# MOSFET_Driver_Sheet1.net
KiCad netlist of a schematic drawn in Altium Designer
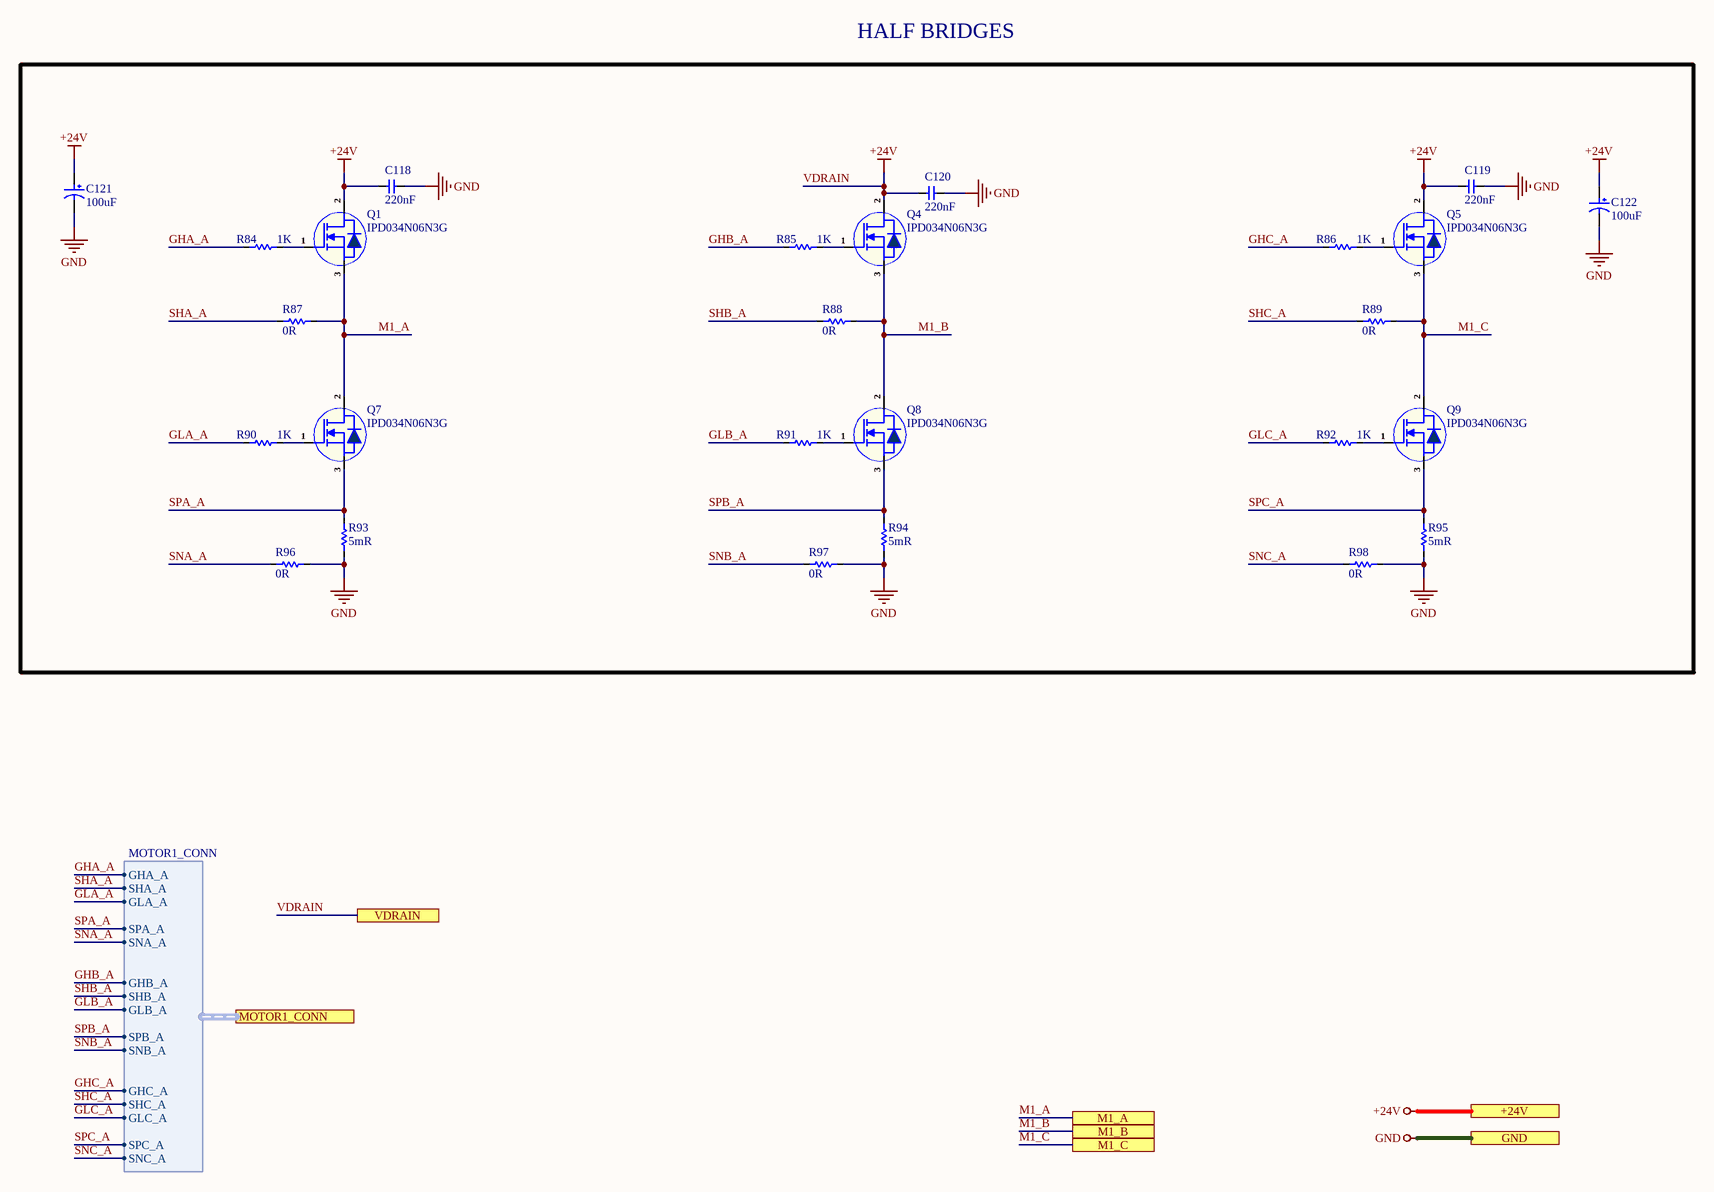
[diagram p0: MOSFET_Driver_Sheet1.SchDoc]

(export (version "E")
  (design (tool "Eeschema 10.0.6"))
  (components
    (comp (ref "C118")
      (value "220nF")
      (footprint "Cap-0805")
      (description "CAP CER 0.22UF 100V X7R 0805")
      (fields
        (field (name "MANUFACTURER") "Kyocera AVX")
        (field (name "MANUFACTURER PART NUMBER") "08051C224K4T2A")
      )
      (libsource (lib "eSpark Libraries") (part "08051C224K4T2A"))
    )
    (comp (ref "C119")
      (value "220nF")
      (footprint "Cap-0805")
      (description "CAP CER 0.22UF 100V X7R 0805")
      (fields
        (field (name "MANUFACTURER") "Kyocera AVX")
        (field (name "MANUFACTURER PART NUMBER") "08051C224K4T2A")
      )
      (libsource (lib "eSpark Libraries") (part "08051C224K4T2A"))
    )
    (comp (ref "C120")
      (value "220nF")
      (footprint "Cap-0805")
      (description "CAP CER 0.22UF 100V X7R 0805")
      (fields
        (field (name "MANUFACTURER") "Kyocera AVX")
        (field (name "MANUFACTURER PART NUMBER") "08051C224K4T2A")
      )
      (libsource (lib "eSpark Libraries") (part "08051C224K4T2A"))
    )
    (comp (ref "C121")
      (value "100uF")
      (footprint "RVT1A101M0605")
      (description "100uF 10V 55mA@120Hz ±20% SMD,D6.3xL5.4mm Aluminum Electrolytic Capacitors - SMD ROHS")
      (fields
        (field (name "MANUFACTURER") "ROQANG")
        (field (name "MANUFACTURER PART NUMBER") "RVT1A101M0605")
      )
      (libsource (lib "eSpark Libraries") (part "RVT1A101M0605"))
    )
    (comp (ref "C122")
      (value "100uF")
      (footprint "RVT1A101M0605")
      (description "100uF 10V 55mA@120Hz ±20% SMD,D6.3xL5.4mm Aluminum Electrolytic Capacitors - SMD ROHS")
      (fields
        (field (name "MANUFACTURER") "ROQANG")
        (field (name "MANUFACTURER PART NUMBER") "RVT1A101M0605")
      )
      (libsource (lib "eSpark Libraries") (part "RVT1A101M0605"))
    )
    (comp (ref "Q1")
      (value "IPD034N06N3G")
      (footprint "TO-252-2L")
      (description "MOSFET N-CH 60V 100A TO252-3")
      (fields (field (name "MANUFACTURER") "Infineon") (field (name "LCSC PART NUMBER") "C94897"))
      (libsource (lib "eSpark Libraries") (part "IPD034N06N3G"))
    )
    (comp (ref "Q4")
      (value "IPD034N06N3G")
      (footprint "TO-252-2L")
      (description "MOSFET N-CH 60V 100A TO252-3")
      (fields (field (name "MANUFACTURER") "Infineon") (field (name "LCSC PART NUMBER") "C94897"))
      (libsource (lib "eSpark Libraries") (part "IPD034N06N3G"))
    )
    (comp (ref "Q5")
      (value "IPD034N06N3G")
      (footprint "TO-252-2L")
      (description "MOSFET N-CH 60V 100A TO252-3")
      (fields (field (name "MANUFACTURER") "Infineon") (field (name "LCSC PART NUMBER") "C94897"))
      (libsource (lib "eSpark Libraries") (part "IPD034N06N3G"))
    )
    (comp (ref "Q7")
      (value "IPD034N06N3G")
      (footprint "TO-252-2L")
      (description "MOSFET N-CH 60V 100A TO252-3")
      (fields (field (name "MANUFACTURER") "Infineon") (field (name "LCSC PART NUMBER") "C94897"))
      (libsource (lib "eSpark Libraries") (part "IPD034N06N3G"))
    )
    (comp (ref "Q8")
      (value "IPD034N06N3G")
      (footprint "TO-252-2L")
      (description "MOSFET N-CH 60V 100A TO252-3")
      (fields (field (name "MANUFACTURER") "Infineon") (field (name "LCSC PART NUMBER") "C94897"))
      (libsource (lib "eSpark Libraries") (part "IPD034N06N3G"))
    )
    (comp (ref "Q9")
      (value "IPD034N06N3G")
      (footprint "TO-252-2L")
      (description "MOSFET N-CH 60V 100A TO252-3")
      (fields (field (name "MANUFACTURER") "Infineon") (field (name "LCSC PART NUMBER") "C94897"))
      (libsource (lib "eSpark Libraries") (part "IPD034N06N3G"))
    )
    (comp (ref "R84")
      (value "1K")
      (footprint "Res-0402")
      (description "RES 1K OHM 1% 1/16W 0402")
      (fields
        (field (name "MANUFACTURER") "Yageo")
        (field (name "MANUFACTURER PART NUMBER") "RC0402FR-071KL")
      )
      (libsource (lib "eSpark Libraries") (part "RC0402FR-071KL"))
    )
    (comp (ref "R85")
      (value "1K")
      (footprint "Res-0402")
      (description "RES 1K OHM 1% 1/16W 0402")
      (fields
        (field (name "MANUFACTURER") "Yageo")
        (field (name "MANUFACTURER PART NUMBER") "RC0402FR-071KL")
      )
      (libsource (lib "eSpark Libraries") (part "RC0402FR-071KL"))
    )
    (comp (ref "R86")
      (value "1K")
      (footprint "Res-0402")
      (description "RES 1K OHM 1% 1/16W 0402")
      (fields
        (field (name "MANUFACTURER") "Yageo")
        (field (name "MANUFACTURER PART NUMBER") "RC0402FR-071KL")
      )
      (libsource (lib "eSpark Libraries") (part "RC0402FR-071KL"))
    )
    (comp (ref "R87")
      (value "0R")
      (footprint "Res-0603")
      (description "RES 0 OHM JUMPER 1/10W 0603")
      (fields
        (field (name "MANUFACTURER") "Yageo")
        (field (name "MANUFACTURER PART NUMBER") "RC0603JR-070RL")
      )
      (libsource (lib "eSpark Libraries") (part "RC0603JR-070RL"))
    )
    (comp (ref "R88")
      (value "0R")
      (footprint "Res-0603")
      (description "RES 0 OHM JUMPER 1/10W 0603")
      (fields
        (field (name "MANUFACTURER") "Yageo")
        (field (name "MANUFACTURER PART NUMBER") "RC0603JR-070RL")
      )
      (libsource (lib "eSpark Libraries") (part "RC0603JR-070RL"))
    )
    (comp (ref "R89")
      (value "0R")
      (footprint "Res-0603")
      (description "RES 0 OHM JUMPER 1/10W 0603")
      (fields
        (field (name "MANUFACTURER") "Yageo")
        (field (name "MANUFACTURER PART NUMBER") "RC0603JR-070RL")
      )
      (libsource (lib "eSpark Libraries") (part "RC0603JR-070RL"))
    )
    (comp (ref "R90")
      (value "1K")
      (footprint "Res-0402")
      (description "RES 1K OHM 1% 1/16W 0402")
      (fields
        (field (name "MANUFACTURER") "Yageo")
        (field (name "MANUFACTURER PART NUMBER") "RC0402FR-071KL")
      )
      (libsource (lib "eSpark Libraries") (part "RC0402FR-071KL"))
    )
    (comp (ref "R91")
      (value "1K")
      (footprint "Res-0402")
      (description "RES 1K OHM 1% 1/16W 0402")
      (fields
        (field (name "MANUFACTURER") "Yageo")
        (field (name "MANUFACTURER PART NUMBER") "RC0402FR-071KL")
      )
      (libsource (lib "eSpark Libraries") (part "RC0402FR-071KL"))
    )
    (comp (ref "R92")
      (value "1K")
      (footprint "Res-0402")
      (description "RES 1K OHM 1% 1/16W 0402")
      (fields
        (field (name "MANUFACTURER") "Yageo")
        (field (name "MANUFACTURER PART NUMBER") "RC0402FR-071KL")
      )
      (libsource (lib "eSpark Libraries") (part "RC0402FR-071KL"))
    )
    (comp (ref "R93")
      (value "5mR")
      (footprint "Res-1206")
      (description "1W 5mΩ ±1% 1206 Current Sense Resistors/Shunt Resistors ROHS")
      (fields
        (field (name "MANUFACTURER") "FORT")
        (field (name "MANUFACTURER PART NUMBER") "CUM1206-15FR005")
      )
      (libsource (lib "eSpark Libraries") (part "CUM1206-15FR005"))
    )
    (comp (ref "R94")
      (value "5mR")
      (footprint "Res-1206")
      (description "1W 5mΩ ±1% 1206 Current Sense Resistors/Shunt Resistors ROHS")
      (fields
        (field (name "MANUFACTURER") "FORT")
        (field (name "MANUFACTURER PART NUMBER") "CUM1206-15FR005")
      )
      (libsource (lib "eSpark Libraries") (part "CUM1206-15FR005"))
    )
    (comp (ref "R95")
      (value "5mR")
      (footprint "Res-1206")
      (description "1W 5mΩ ±1% 1206 Current Sense Resistors/Shunt Resistors ROHS")
      (fields
        (field (name "MANUFACTURER") "FORT")
        (field (name "MANUFACTURER PART NUMBER") "CUM1206-15FR005")
      )
      (libsource (lib "eSpark Libraries") (part "CUM1206-15FR005"))
    )
    (comp (ref "R96")
      (value "0R")
      (footprint "Res-0603")
      (description "RES 0 OHM JUMPER 1/10W 0603")
      (fields
        (field (name "MANUFACTURER") "Yageo")
        (field (name "MANUFACTURER PART NUMBER") "RC0603JR-070RL")
      )
      (libsource (lib "eSpark Libraries") (part "RC0603JR-070RL"))
    )
    (comp (ref "R97")
      (value "0R")
      (footprint "Res-0603")
      (description "RES 0 OHM JUMPER 1/10W 0603")
      (fields
        (field (name "MANUFACTURER") "Yageo")
        (field (name "MANUFACTURER PART NUMBER") "RC0603JR-070RL")
      )
      (libsource (lib "eSpark Libraries") (part "RC0603JR-070RL"))
    )
    (comp (ref "R98")
      (value "0R")
      (footprint "Res-0603")
      (description "RES 0 OHM JUMPER 1/10W 0603")
      (fields
        (field (name "MANUFACTURER") "Yageo")
        (field (name "MANUFACTURER PART NUMBER") "RC0603JR-070RL")
      )
      (libsource (lib "eSpark Libraries") (part "RC0603JR-070RL"))
    )
  )
  (nets
    (net (code "2") (name "+24V") (class "Default")
      (node (ref "C118") (pin "2") (pinfunction "2_2") (pintype "passive"))
      (node (ref "C119") (pin "2") (pinfunction "2_2") (pintype "passive"))
      (node (ref "C120") (pin "2") (pinfunction "2_2") (pintype "passive"))
      (node (ref "C121") (pin "1") (pintype "passive"))
      (node (ref "C122") (pin "1") (pintype "passive"))
      (node (ref "Q1") (pin "2") (pinfunction "D_2") (pintype "passive"))
      (node (ref "Q4") (pin "2") (pinfunction "D_2") (pintype "passive"))
      (node (ref "Q5") (pin "2") (pinfunction "D_2") (pintype "passive"))
    )
    (net (code "3") (name "/GHA_A") (class "Default")
      (node (ref "R84") (pin "1") (pinfunction "1_1") (pintype "passive"))
    )
    (net (code "4") (name "/GHB_A") (class "Default")
      (node (ref "R85") (pin "1") (pinfunction "1_1") (pintype "passive"))
    )
    (net (code "5") (name "/GHC_A") (class "Default")
      (node (ref "R86") (pin "1") (pinfunction "1_1") (pintype "passive"))
    )
    (net (code "6") (name "/GLA_A") (class "Default")
      (node (ref "R90") (pin "1") (pinfunction "1_1") (pintype "passive"))
    )
    (net (code "7") (name "/GLB_A") (class "Default")
      (node (ref "R91") (pin "1") (pinfunction "1_1") (pintype "passive"))
    )
    (net (code "8") (name "/GLC_A") (class "Default")
      (node (ref "R92") (pin "1") (pinfunction "1_1") (pintype "passive"))
    )
    (net (code "9") (name "/M1_A") (class "Default")
      (node (ref "Q1") (pin "3") (pinfunction "S_3") (pintype "passive"))
      (node (ref "Q7") (pin "2") (pinfunction "D_2") (pintype "passive"))
      (node (ref "R87") (pin "1") (pinfunction "1_1") (pintype "passive"))
    )
    (net (code "10") (name "/M1_B") (class "Default")
      (node (ref "Q4") (pin "3") (pinfunction "S_3") (pintype "passive"))
      (node (ref "Q8") (pin "2") (pinfunction "D_2") (pintype "passive"))
      (node (ref "R88") (pin "1") (pinfunction "1_1") (pintype "passive"))
    )
    (net (code "11") (name "/M1_C") (class "Default")
      (node (ref "Q5") (pin "3") (pinfunction "S_3") (pintype "passive"))
      (node (ref "Q9") (pin "2") (pinfunction "D_2") (pintype "passive"))
      (node (ref "R89") (pin "1") (pinfunction "1_1") (pintype "passive"))
    )
    (net (code "12") (name "/SHA_A") (class "Default")
      (node (ref "R87") (pin "2") (pinfunction "2_2") (pintype "passive"))
    )
    (net (code "13") (name "/SHB_A") (class "Default")
      (node (ref "R88") (pin "2") (pinfunction "2_2") (pintype "passive"))
    )
    (net (code "14") (name "/SHC_A") (class "Default")
      (node (ref "R89") (pin "2") (pinfunction "2_2") (pintype "passive"))
    )
    (net (code "15") (name "/SNA_A") (class "Default")
      (node (ref "R96") (pin "2") (pinfunction "2_2") (pintype "passive"))
    )
    (net (code "16") (name "/SNB_A") (class "Default")
      (node (ref "R97") (pin "2") (pinfunction "2_2") (pintype "passive"))
    )
    (net (code "17") (name "/SNC_A") (class "Default")
      (node (ref "R98") (pin "2") (pinfunction "2_2") (pintype "passive"))
    )
    (net (code "18") (name "/SPA_A") (class "Default")
      (node (ref "Q7") (pin "3") (pinfunction "S_3") (pintype "passive"))
      (node (ref "R93") (pin "2") (pinfunction "2_2") (pintype "passive"))
    )
    (net (code "19") (name "/SPB_A") (class "Default")
      (node (ref "Q8") (pin "3") (pinfunction "S_3") (pintype "passive"))
      (node (ref "R94") (pin "2") (pinfunction "2_2") (pintype "passive"))
    )
    (net (code "20") (name "/SPC_A") (class "Default")
      (node (ref "Q9") (pin "3") (pinfunction "S_3") (pintype "passive"))
      (node (ref "R95") (pin "2") (pinfunction "2_2") (pintype "passive"))
    )
    (net (code "22") (name "GND") (class "Default")
      (node (ref "C118") (pin "1") (pinfunction "1_1") (pintype "passive"))
      (node (ref "C119") (pin "1") (pinfunction "1_1") (pintype "passive"))
      (node (ref "C120") (pin "1") (pinfunction "1_1") (pintype "passive"))
      (node (ref "C121") (pin "2") (pintype "passive"))
      (node (ref "C122") (pin "2") (pintype "passive"))
      (node (ref "R93") (pin "1") (pinfunction "1_1") (pintype "passive"))
      (node (ref "R94") (pin "1") (pinfunction "1_1") (pintype "passive"))
      (node (ref "R95") (pin "1") (pinfunction "1_1") (pintype "passive"))
      (node (ref "R96") (pin "1") (pinfunction "1_1") (pintype "passive"))
      (node (ref "R97") (pin "1") (pinfunction "1_1") (pintype "passive"))
      (node (ref "R98") (pin "1") (pinfunction "1_1") (pintype "passive"))
    )
    (net (code "23") (name "Net-(Q1-G)") (class "Default")
      (node (ref "Q1") (pin "1") (pinfunction "G_1") (pintype "passive"))
      (node (ref "R84") (pin "2") (pinfunction "2_2") (pintype "passive"))
    )
    (net (code "24") (name "Net-(Q4-G)") (class "Default")
      (node (ref "Q4") (pin "1") (pinfunction "G_1") (pintype "passive"))
      (node (ref "R85") (pin "2") (pinfunction "2_2") (pintype "passive"))
    )
    (net (code "25") (name "Net-(Q5-G)") (class "Default")
      (node (ref "Q5") (pin "1") (pinfunction "G_1") (pintype "passive"))
      (node (ref "R86") (pin "2") (pinfunction "2_2") (pintype "passive"))
    )
    (net (code "26") (name "Net-(Q7-G)") (class "Default")
      (node (ref "Q7") (pin "1") (pinfunction "G_1") (pintype "passive"))
      (node (ref "R90") (pin "2") (pinfunction "2_2") (pintype "passive"))
    )
    (net (code "27") (name "Net-(Q8-G)") (class "Default")
      (node (ref "Q8") (pin "1") (pinfunction "G_1") (pintype "passive"))
      (node (ref "R91") (pin "2") (pinfunction "2_2") (pintype "passive"))
    )
    (net (code "28") (name "Net-(Q9-G)") (class "Default")
      (node (ref "Q9") (pin "1") (pinfunction "G_1") (pintype "passive"))
      (node (ref "R92") (pin "2") (pinfunction "2_2") (pintype "passive"))
    )
  )
)
